# REG_Sheet.net
KiCad netlist of a schematic drawn in Altium Designer
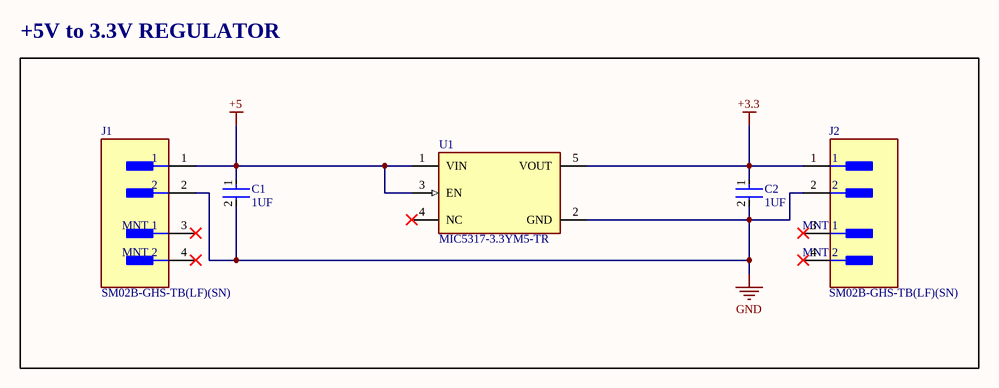
[diagram p0: REG_Sheet.SchDoc]

(export (version "E")
  (design (tool "Eeschema 10.0.6"))
  (components
    (comp (ref "C1")
      (value "1UF")
      (footprint "FP-CC0805-0_85-MFG")
      (description "CAP CER 1UF 10V X7R 0805")
      (fields
        (field (name "MANUFACTURER") "Yageo")
        (field (name "OCTOPART") "https://octopart.com/cc0805kkx7r6bb105-yageo-42522859")
      )
      (libsource (lib "Altium Content Vault") (part "11868f565c42a9108669ba33697ecf6"))
    )
    (comp (ref "C2")
      (value "1UF")
      (footprint "FP-CC0805-0_85-MFG")
      (description "CAP CER 1UF 10V X7R 0805")
      (fields
        (field (name "MANUFACTURER") "Yageo")
        (field (name "OCTOPART") "https://octopart.com/cc0805kkx7r6bb105-yageo-42522859")
      )
      (libsource (lib "Altium Content Vault") (part "11868f565c42a9108669ba33697ecf6"))
    )
    (comp (ref "J1")
      (value "SM02B-GHS-TB(LF)(SN)")
      (footprint "FP-SM02B-GHS-TB_LF_SN-MFG")
      (description "CONN HEADER SMD R/A 2POS 1.25MM")
      (libsource (lib "") (part "56ec3178a87b3978bdc1b3682cd516a_1"))
    )
    (comp (ref "J2")
      (value "SM02B-GHS-TB(LF)(SN)")
      (footprint "FP-SM02B-GHS-TB_LF_SN-MFG")
      (description "CONN HEADER SMD R/A 2POS 1.25MM")
      (libsource (lib "Altium Content Vault") (part "56ec3178a87b3978bdc1b3682cd516a"))
    )
    (comp (ref "U1")
      (value "MIC5317-3.3YM5-TR")
      (footprint "FP-SOT23-5LD-PL-1-MFG")
      (description "IC REG LINEAR 3.3V 150MA SOT23-5")
      (libsource (lib "Altium Content Vault") (part "0a093dae7315cdc977fd108dde87457"))
    )
  )
  (nets
    (net (code "1") (name "+3.3") (class "Default")
      (node (ref "C2") (pin "1") (pinfunction "1_1") (pintype "passive"))
      (node (ref "J2") (pin "1") (pinfunction "1_1") (pintype "passive"))
      (node (ref "U1") (pin "5") (pinfunction "VOUT_5") (pintype "power_in"))
    )
    (net (code "2") (name "+5") (class "Default")
      (node (ref "C1") (pin "1") (pinfunction "1_1") (pintype "passive"))
      (node (ref "J1") (pin "1") (pinfunction "1_1") (pintype "passive"))
      (node (ref "U1") (pin "1") (pinfunction "VIN_1") (pintype "power_in"))
      (node (ref "U1") (pin "3") (pinfunction "EN_3") (pintype "input"))
    )
    (net (code "3") (name "GND") (class "Default")
      (node (ref "C1") (pin "2") (pinfunction "2_2") (pintype "passive"))
      (node (ref "C2") (pin "2") (pinfunction "2_2") (pintype "passive"))
      (node (ref "J1") (pin "2") (pinfunction "2_2") (pintype "passive"))
      (node (ref "J2") (pin "2") (pinfunction "2_2") (pintype "passive"))
      (node (ref "U1") (pin "2") (pinfunction "GND_2") (pintype "power_in"))
    )
    (net (code "4") (name "unconnected-(J1-MNT_1-Pad3)") (class "Default")
      (node (ref "J1") (pin "3") (pinfunction "MNT_1_3") (pintype "passive+no_connect"))
    )
    (net (code "5") (name "unconnected-(J1-MNT_2-Pad4)") (class "Default")
      (node (ref "J1") (pin "4") (pinfunction "MNT_2_4") (pintype "passive+no_connect"))
    )
    (net (code "6") (name "unconnected-(J2-MNT_1-Pad3)") (class "Default")
      (node (ref "J2") (pin "3") (pinfunction "MNT_1_3") (pintype "passive+no_connect"))
    )
    (net (code "7") (name "unconnected-(J2-MNT_2-Pad4)") (class "Default")
      (node (ref "J2") (pin "4") (pinfunction "MNT_2_4") (pintype "passive+no_connect"))
    )
    (net (code "8") (name "unconnected-(U1-NC-Pad4)") (class "Default")
      (node (ref "U1") (pin "4") (pinfunction "NC_4") (pintype "passive+no_connect"))
    )
  )
)
